# nrfKey_2401.net
KiCad netlist of a schematic drawn in EAGLE
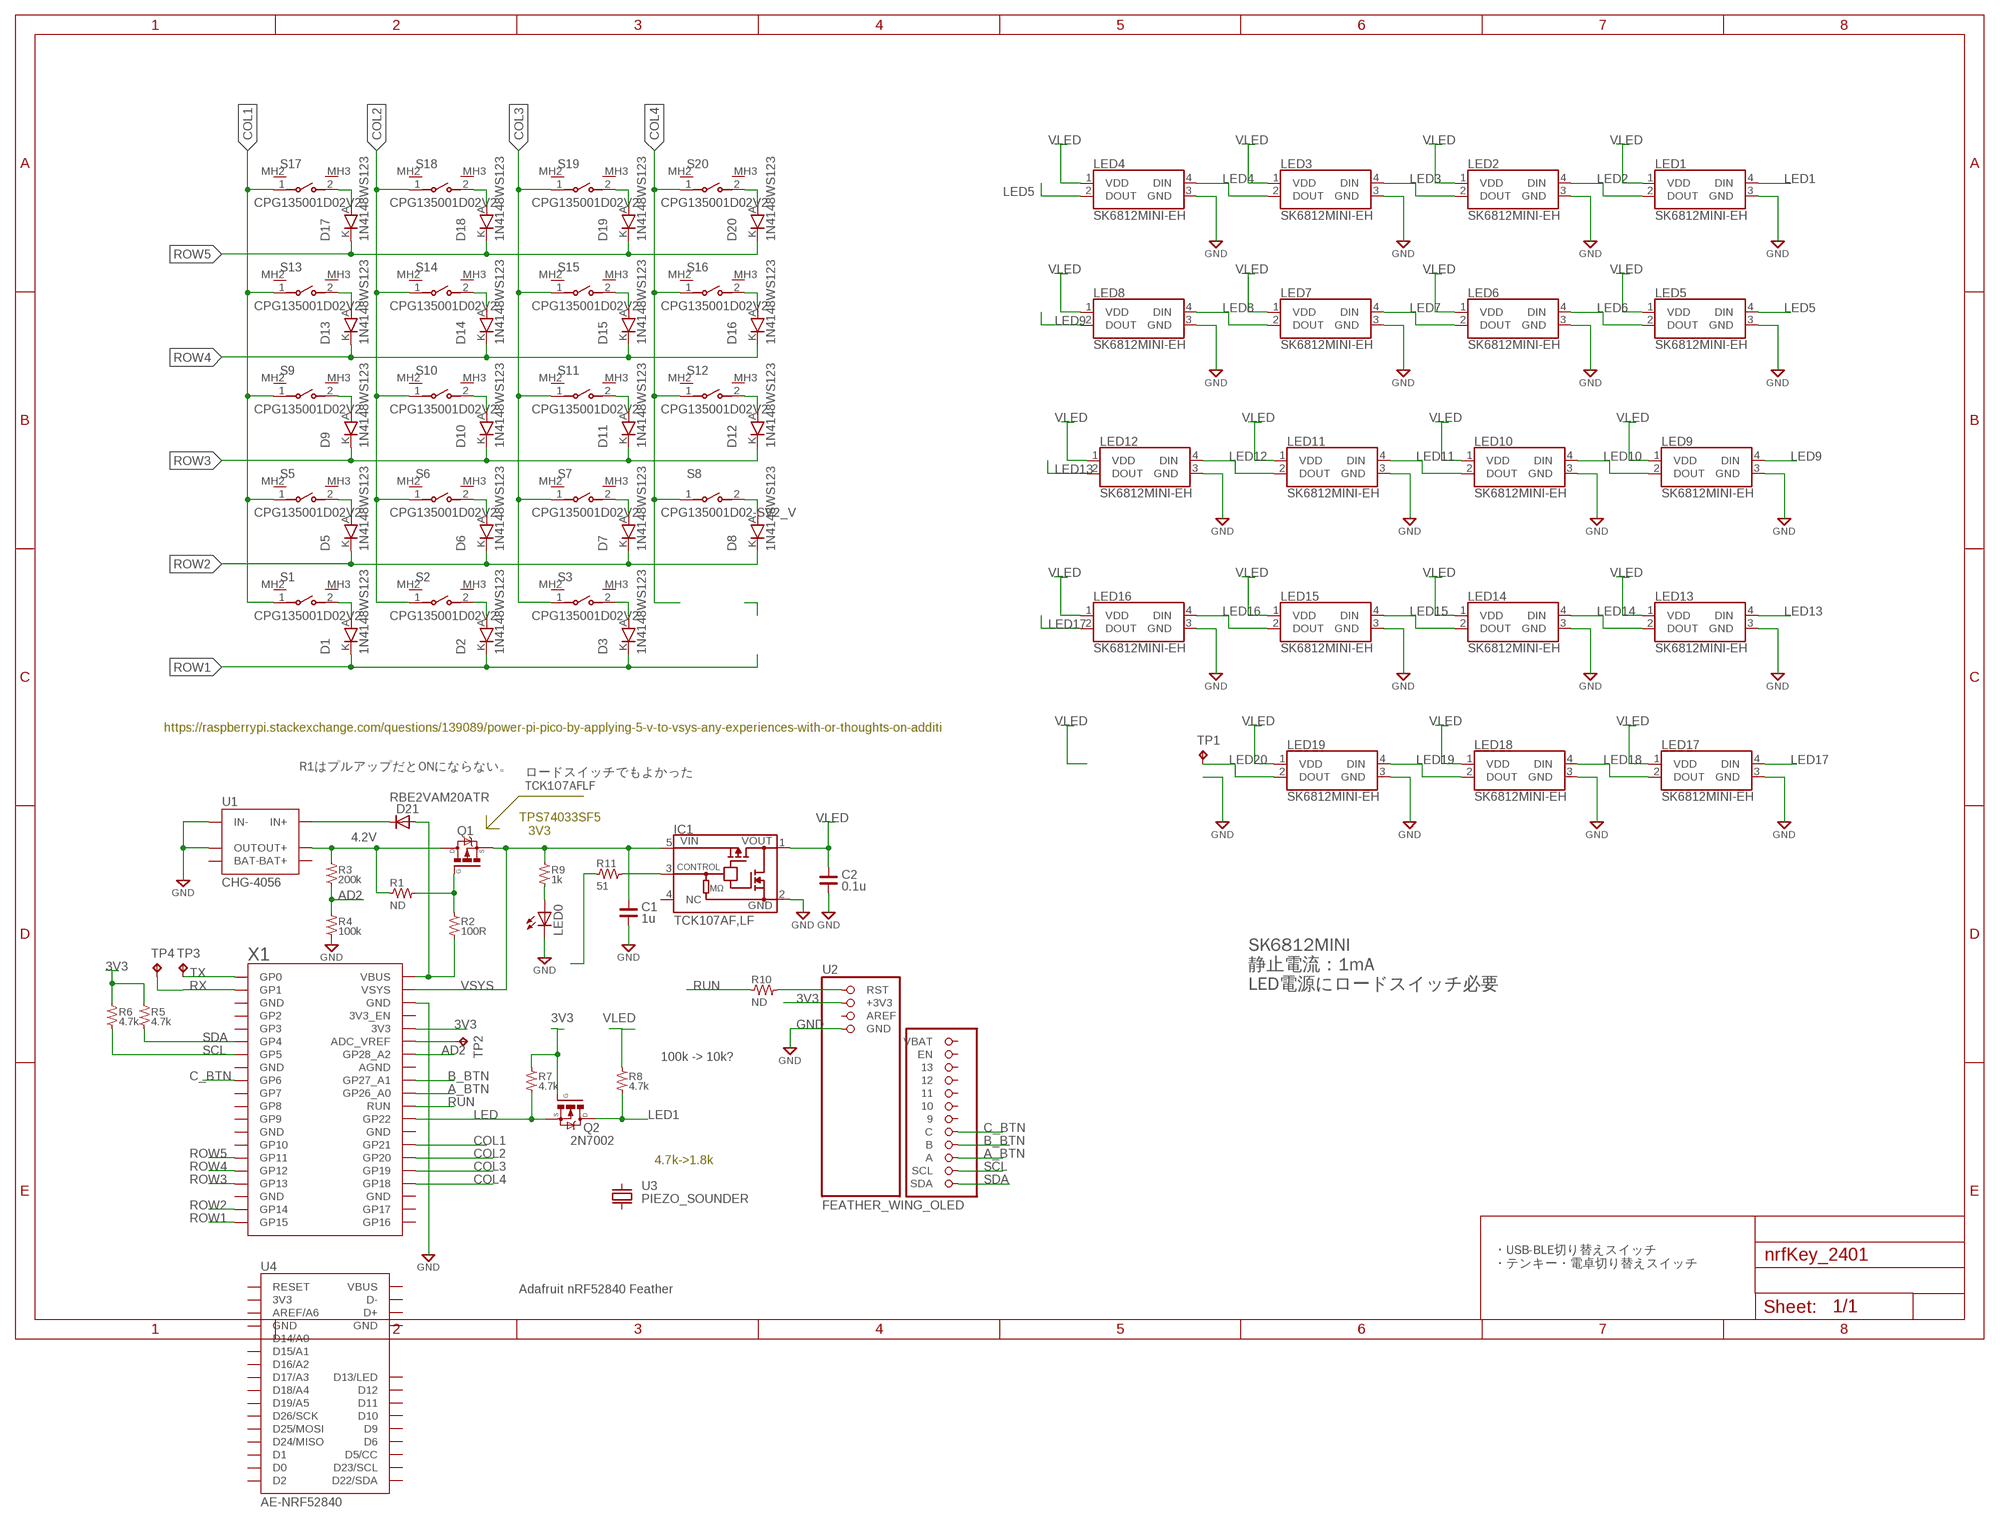
[diagram p0: schematic, sheet 1]

(export (version "E")
  (design (tool "Eeschema 10.0.6"))
  (components
    (comp (ref "C1")
      (value "1u")
      (footprint "eagle-import:C0603")
      (libsource (lib "eagle-import") (part "C_0603"))
    )
    (comp (ref "C2")
      (value "0.1u")
      (footprint "eagle-import:C0603")
      (libsource (lib "eagle-import") (part "C_0603"))
    )
    (comp (ref "D1")
      (value "1N4148WS123")
      (footprint "eagle-import:SOD-123")
      (libsource (lib "eagle-import") (part "1N4148WS123"))
    )
    (comp (ref "D2")
      (value "1N4148WS123")
      (footprint "eagle-import:SOD-123")
      (libsource (lib "eagle-import") (part "1N4148WS123"))
    )
    (comp (ref "D3")
      (value "1N4148WS123")
      (footprint "eagle-import:SOD-123")
      (libsource (lib "eagle-import") (part "1N4148WS123"))
    )
    (comp (ref "D5")
      (value "1N4148WS123")
      (footprint "eagle-import:SOD-123")
      (libsource (lib "eagle-import") (part "1N4148WS123"))
    )
    (comp (ref "D6")
      (value "1N4148WS123")
      (footprint "eagle-import:SOD-123")
      (libsource (lib "eagle-import") (part "1N4148WS123"))
    )
    (comp (ref "D7")
      (value "1N4148WS123")
      (footprint "eagle-import:SOD-123")
      (libsource (lib "eagle-import") (part "1N4148WS123"))
    )
    (comp (ref "D8")
      (value "1N4148WS123")
      (footprint "eagle-import:SOD-123")
      (libsource (lib "eagle-import") (part "1N4148WS123"))
    )
    (comp (ref "D9")
      (value "1N4148WS123")
      (footprint "eagle-import:SOD-123")
      (libsource (lib "eagle-import") (part "1N4148WS123"))
    )
    (comp (ref "D10")
      (value "1N4148WS123")
      (footprint "eagle-import:SOD-123")
      (libsource (lib "eagle-import") (part "1N4148WS123"))
    )
    (comp (ref "D11")
      (value "1N4148WS123")
      (footprint "eagle-import:SOD-123")
      (libsource (lib "eagle-import") (part "1N4148WS123"))
    )
    (comp (ref "D12")
      (value "1N4148WS123")
      (footprint "eagle-import:SOD-123")
      (libsource (lib "eagle-import") (part "1N4148WS123"))
    )
    (comp (ref "D13")
      (value "1N4148WS123")
      (footprint "eagle-import:SOD-123")
      (libsource (lib "eagle-import") (part "1N4148WS123"))
    )
    (comp (ref "D14")
      (value "1N4148WS123")
      (footprint "eagle-import:SOD-123")
      (libsource (lib "eagle-import") (part "1N4148WS123"))
    )
    (comp (ref "D15")
      (value "1N4148WS123")
      (footprint "eagle-import:SOD-123")
      (libsource (lib "eagle-import") (part "1N4148WS123"))
    )
    (comp (ref "D16")
      (value "1N4148WS123")
      (footprint "eagle-import:SOD-123")
      (libsource (lib "eagle-import") (part "1N4148WS123"))
    )
    (comp (ref "D17")
      (value "1N4148WS123")
      (footprint "eagle-import:SOD-123")
      (libsource (lib "eagle-import") (part "1N4148WS123"))
    )
    (comp (ref "D18")
      (value "1N4148WS123")
      (footprint "eagle-import:SOD-123")
      (libsource (lib "eagle-import") (part "1N4148WS123"))
    )
    (comp (ref "D19")
      (value "1N4148WS123")
      (footprint "eagle-import:SOD-123")
      (libsource (lib "eagle-import") (part "1N4148WS123"))
    )
    (comp (ref "D20")
      (value "1N4148WS123")
      (footprint "eagle-import:SOD-123")
      (libsource (lib "eagle-import") (part "1N4148WS123"))
    )
    (comp (ref "D21")
      (value "RBE2VAM20ATR")
      (footprint "eagle-import:SOD-123")
      (libsource (lib "eagle-import") (part "DIODE123"))
    )
    (comp (ref "IC1")
      (value "TCK107AF,LF")
      (footprint "eagle-import:SMV_1")
      (fields
        (field (name "ARROW_PART_NUMBER") "TCK106AF,LF")
        (field (name "MOUSER_PART_NUMBER") "757-TCK106AFLF")
      )
      (libsource (lib "eagle-import") (part "TCK107AF,LF"))
    )
    (comp (ref "LED0")
      (value "LEDCHIP-LED0603")
      (footprint "eagle-import:CHIP-LED0603")
      (libsource (lib "eagle-import") (part "LEDCHIP-LED0603"))
    )
    (comp (ref "LED1")
      (value "SK6812MINI-EH")
      (footprint "eagle-import:SK6812MINIE-H")
      (libsource (lib "eagle-import") (part "SK6812MINI-EH"))
    )
    (comp (ref "LED2")
      (value "SK6812MINI-EH")
      (footprint "eagle-import:SK6812MINIE-H")
      (libsource (lib "eagle-import") (part "SK6812MINI-EH"))
    )
    (comp (ref "LED3")
      (value "SK6812MINI-EH")
      (footprint "eagle-import:SK6812MINIE-H")
      (libsource (lib "eagle-import") (part "SK6812MINI-EH"))
    )
    (comp (ref "LED4")
      (value "SK6812MINI-EH")
      (footprint "eagle-import:SK6812MINIE-H")
      (libsource (lib "eagle-import") (part "SK6812MINI-EH"))
    )
    (comp (ref "LED5")
      (value "SK6812MINI-EH")
      (footprint "eagle-import:SK6812MINIE-H")
      (libsource (lib "eagle-import") (part "SK6812MINI-EH"))
    )
    (comp (ref "LED6")
      (value "SK6812MINI-EH")
      (footprint "eagle-import:SK6812MINIE-H")
      (libsource (lib "eagle-import") (part "SK6812MINI-EH"))
    )
    (comp (ref "LED7")
      (value "SK6812MINI-EH")
      (footprint "eagle-import:SK6812MINIE-H")
      (libsource (lib "eagle-import") (part "SK6812MINI-EH"))
    )
    (comp (ref "LED8")
      (value "SK6812MINI-EH")
      (footprint "eagle-import:SK6812MINIE-H")
      (libsource (lib "eagle-import") (part "SK6812MINI-EH"))
    )
    (comp (ref "LED9")
      (value "SK6812MINI-EH")
      (footprint "eagle-import:SK6812MINIE-H")
      (libsource (lib "eagle-import") (part "SK6812MINI-EH"))
    )
    (comp (ref "LED10")
      (value "SK6812MINI-EH")
      (footprint "eagle-import:SK6812MINIE-H")
      (libsource (lib "eagle-import") (part "SK6812MINI-EH"))
    )
    (comp (ref "LED11")
      (value "SK6812MINI-EH")
      (footprint "eagle-import:SK6812MINIE-H")
      (libsource (lib "eagle-import") (part "SK6812MINI-EH"))
    )
    (comp (ref "LED12")
      (value "SK6812MINI-EH")
      (footprint "eagle-import:SK6812MINIE-H")
      (libsource (lib "eagle-import") (part "SK6812MINI-EH"))
    )
    (comp (ref "LED13")
      (value "SK6812MINI-EH")
      (footprint "eagle-import:SK6812MINIE-H")
      (libsource (lib "eagle-import") (part "SK6812MINI-EH"))
    )
    (comp (ref "LED14")
      (value "SK6812MINI-EH")
      (footprint "eagle-import:SK6812MINIE-H")
      (libsource (lib "eagle-import") (part "SK6812MINI-EH"))
    )
    (comp (ref "LED15")
      (value "SK6812MINI-EH")
      (footprint "eagle-import:SK6812MINIE-H")
      (libsource (lib "eagle-import") (part "SK6812MINI-EH"))
    )
    (comp (ref "LED16")
      (value "SK6812MINI-EH")
      (footprint "eagle-import:SK6812MINIE-H")
      (libsource (lib "eagle-import") (part "SK6812MINI-EH"))
    )
    (comp (ref "LED17")
      (value "SK6812MINI-EH")
      (footprint "eagle-import:SK6812MINIE-H")
      (libsource (lib "eagle-import") (part "SK6812MINI-EH"))
    )
    (comp (ref "LED18")
      (value "SK6812MINI-EH")
      (footprint "eagle-import:SK6812MINIE-H")
      (libsource (lib "eagle-import") (part "SK6812MINI-EH"))
    )
    (comp (ref "LED19")
      (value "SK6812MINI-EH")
      (footprint "eagle-import:SK6812MINIE-H")
      (libsource (lib "eagle-import") (part "SK6812MINI-EH"))
    )
    (comp (ref "Q1")
      (value "MOSFET-P")
      (footprint "eagle-import:SOT-23")
      (libsource (lib "eagle-import") (part "MOSFET-P"))
    )
    (comp (ref "Q2")
      (value "2N7002")
      (footprint "eagle-import:SOT-23")
      (libsource (lib "eagle-import") (part "MOSFET-NSOT-23"))
    )
    (comp (ref "R1")
      (value "ND")
      (footprint "eagle-import:R0603")
      (libsource (lib "eagle-import") (part "R_0603"))
    )
    (comp (ref "R2")
      (value "100R")
      (footprint "eagle-import:R0603")
      (libsource (lib "eagle-import") (part "R_0603"))
    )
    (comp (ref "R3")
      (value "200k")
      (footprint "eagle-import:R0603")
      (libsource (lib "eagle-import") (part "R_0603"))
    )
    (comp (ref "R4")
      (value "100k")
      (footprint "eagle-import:R0603")
      (libsource (lib "eagle-import") (part "R_0603"))
    )
    (comp (ref "R5")
      (value "4.7k")
      (footprint "eagle-import:R0603")
      (libsource (lib "eagle-import") (part "R_0603"))
    )
    (comp (ref "R6")
      (value "4.7k")
      (footprint "eagle-import:R0603")
      (libsource (lib "eagle-import") (part "R_0603"))
    )
    (comp (ref "R7")
      (value "4.7k")
      (footprint "eagle-import:R0603")
      (libsource (lib "eagle-import") (part "R_0603"))
    )
    (comp (ref "R8")
      (value "4.7k")
      (footprint "eagle-import:R0603")
      (libsource (lib "eagle-import") (part "R_0603"))
    )
    (comp (ref "R9")
      (value "1k")
      (footprint "eagle-import:R0603")
      (libsource (lib "eagle-import") (part "R_0603"))
    )
    (comp (ref "R10")
      (value "ND")
      (footprint "eagle-import:R0603")
      (libsource (lib "eagle-import") (part "R_0603"))
    )
    (comp (ref "R11")
      (value "51")
      (footprint "eagle-import:R0603")
      (libsource (lib "eagle-import") (part "R_0603"))
    )
    (comp (ref "S1")
      (value "CPG135001D02V2")
      (footprint "eagle-import:KAILH_CHOC_V2")
      (libsource (lib "eagle-import") (part "CPG135001D02V2"))
    )
    (comp (ref "S2")
      (value "CPG135001D02V2")
      (footprint "eagle-import:KAILH_CHOC_V2")
      (libsource (lib "eagle-import") (part "CPG135001D02V2"))
    )
    (comp (ref "S3")
      (value "CPG135001D02V2")
      (footprint "eagle-import:KAILH_CHOC_V2")
      (libsource (lib "eagle-import") (part "CPG135001D02V2"))
    )
    (comp (ref "S5")
      (value "CPG135001D02V2")
      (footprint "eagle-import:KAILH_CHOC_V2")
      (libsource (lib "eagle-import") (part "CPG135001D02V2"))
    )
    (comp (ref "S6")
      (value "CPG135001D02V2")
      (footprint "eagle-import:KAILH_CHOC_V2")
      (libsource (lib "eagle-import") (part "CPG135001D02V2"))
    )
    (comp (ref "S7")
      (value "CPG135001D02V2")
      (footprint "eagle-import:KAILH_CHOC_V2")
      (libsource (lib "eagle-import") (part "CPG135001D02V2"))
    )
    (comp (ref "S8")
      (value "CPG135001D02-SV2_V")
      (footprint "eagle-import:KAILH_CHOC_V2_V")
      (libsource (lib "eagle-import") (part "CPG135001D02-SV2_V"))
    )
    (comp (ref "S9")
      (value "CPG135001D02V2")
      (footprint "eagle-import:KAILH_CHOC_V2")
      (libsource (lib "eagle-import") (part "CPG135001D02V2"))
    )
    (comp (ref "S10")
      (value "CPG135001D02V2")
      (footprint "eagle-import:KAILH_CHOC_V2")
      (libsource (lib "eagle-import") (part "CPG135001D02V2"))
    )
    (comp (ref "S11")
      (value "CPG135001D02V2")
      (footprint "eagle-import:KAILH_CHOC_V2")
      (libsource (lib "eagle-import") (part "CPG135001D02V2"))
    )
    (comp (ref "S12")
      (value "CPG135001D02V2")
      (footprint "eagle-import:KAILH_CHOC_V2")
      (libsource (lib "eagle-import") (part "CPG135001D02V2"))
    )
    (comp (ref "S13")
      (value "CPG135001D02V2")
      (footprint "eagle-import:KAILH_CHOC_V2")
      (libsource (lib "eagle-import") (part "CPG135001D02V2"))
    )
    (comp (ref "S14")
      (value "CPG135001D02V2")
      (footprint "eagle-import:KAILH_CHOC_V2")
      (libsource (lib "eagle-import") (part "CPG135001D02V2"))
    )
    (comp (ref "S15")
      (value "CPG135001D02V2")
      (footprint "eagle-import:KAILH_CHOC_V2")
      (libsource (lib "eagle-import") (part "CPG135001D02V2"))
    )
    (comp (ref "S16")
      (value "CPG135001D02V2")
      (footprint "eagle-import:KAILH_CHOC_V2")
      (libsource (lib "eagle-import") (part "CPG135001D02V2"))
    )
    (comp (ref "S17")
      (value "CPG135001D02V2")
      (footprint "eagle-import:KAILH_CHOC_V2")
      (libsource (lib "eagle-import") (part "CPG135001D02V2"))
    )
    (comp (ref "S18")
      (value "CPG135001D02V2")
      (footprint "eagle-import:KAILH_CHOC_V2")
      (libsource (lib "eagle-import") (part "CPG135001D02V2"))
    )
    (comp (ref "S19")
      (value "CPG135001D02V2")
      (footprint "eagle-import:KAILH_CHOC_V2")
      (libsource (lib "eagle-import") (part "CPG135001D02V2"))
    )
    (comp (ref "S20")
      (value "CPG135001D02V2")
      (footprint "eagle-import:KAILH_CHOC_V2")
      (libsource (lib "eagle-import") (part "CPG135001D02V2"))
    )
    (comp (ref "TP1")
      (value "TPTP06R")
      (footprint "eagle-import:TP06R")
      (libsource (lib "eagle-import") (part "TPTP06R"))
    )
    (comp (ref "TP2")
      (value "TPTP06R")
      (footprint "eagle-import:TP06R")
      (libsource (lib "eagle-import") (part "TPTP06R"))
    )
    (comp (ref "TP3")
      (value "TPTP06R")
      (footprint "eagle-import:TP06R")
      (libsource (lib "eagle-import") (part "TPTP06R"))
    )
    (comp (ref "TP4")
      (value "TPTP06R")
      (footprint "eagle-import:TP06R")
      (libsource (lib "eagle-import") (part "TPTP06R"))
    )
    (comp (ref "U1")
      (value "CHG-4056")
      (footprint "eagle-import:CHG-4056")
      (libsource (lib "eagle-import") (part "CHG-4056"))
    )
    (comp (ref "U2")
      (value "FEATHER_WING_OLED")
      (footprint "eagle-import:FEATHER_WING_OLED")
      (libsource (lib "eagle-import") (part "FEATHER_WING_OLED"))
    )
    (comp (ref "U3")
      (value "PIEZO_SOUNDER")
      (footprint "eagle-import:DINAMIC-SPK")
      (libsource (lib "eagle-import") (part "PIEZO_SOUNDER"))
    )
    (comp (ref "U4")
      (value "AE-NRF52840")
      (footprint "eagle-import:AE-NRF52840")
      (libsource (lib "eagle-import") (part "AE-NRF52840"))
    )
    (comp (ref "X1")
      (value "RASPBERRYPI_PICO_RPI_PICO_MY-MY")
      (footprint "eagle-import:RASPBERRYPI_PICO_RPI_PICO_MY")
      (libsource (lib "eagle-import") (part "RASPBERRYPI_PICO_RPI_PICO_MY-MY"))
    )
  )
  (nets
    (net (code "1") (name "/3V3") (class "Default")
      (node (ref "Q2") (pin "3") (pinfunction "G_3") (pintype "passive"))
      (node (ref "R5") (pin "2") (pinfunction "2_2") (pintype "passive"))
      (node (ref "R6") (pin "2") (pinfunction "2_2") (pintype "passive"))
      (node (ref "R7") (pin "1") (pinfunction "1_1") (pintype "passive"))
      (node (ref "U2") (pin "15") (pinfunction "+3V3_15") (pintype "passive"))
      (node (ref "X1") (pin "3V3") (pinfunction "3V3_3V3") (pintype "bidirectional"))
    )
    (net (code "2") (name "/4.2V") (class "Default")
      (node (ref "Q1") (pin "2") (pinfunction "D_2") (pintype "passive"))
      (node (ref "R1") (pin "1") (pinfunction "1_1") (pintype "passive"))
      (node (ref "R3") (pin "2") (pinfunction "2_2") (pintype "passive"))
      (node (ref "U1") (pin "OUT+") (pinfunction "OUT+_OUT+") (pintype "bidirectional"))
    )
    (net (code "3") (name "/AD2") (class "Default")
      (node (ref "R3") (pin "1") (pinfunction "1_1") (pintype "passive"))
      (node (ref "R4") (pin "2") (pinfunction "2_2") (pintype "passive"))
      (node (ref "X1") (pin "GP28_A2") (pinfunction "GP28_A2_GP28_A2") (pintype "bidirectional"))
    )
    (net (code "4") (name "/A_BTN") (class "Default")
      (node (ref "U2") (pin "26") (pinfunction "A_26") (pintype "passive"))
      (node (ref "X1") (pin "GP26_A0") (pinfunction "GP26_A0_GP26_A0") (pintype "bidirectional"))
    )
    (net (code "5") (name "/B_BTN") (class "Default")
      (node (ref "U2") (pin "25") (pinfunction "B_25") (pintype "passive"))
      (node (ref "X1") (pin "GP27_A1") (pinfunction "GP27_A1_GP27_A1") (pintype "bidirectional"))
    )
    (net (code "6") (name "/C_BTN") (class "Default")
      (node (ref "U2") (pin "24") (pinfunction "C_24") (pintype "passive"))
      (node (ref "X1") (pin "GP6") (pinfunction "GP6_GP6") (pintype "bidirectional"))
    )
    (net (code "7") (name "/LED") (class "Default")
      (node (ref "Q2") (pin "1") (pinfunction "S_1") (pintype "passive"))
      (node (ref "R7") (pin "2") (pinfunction "2_2") (pintype "passive"))
      (node (ref "X1") (pin "GP22") (pinfunction "GP22_GP22") (pintype "bidirectional"))
    )
    (net (code "8") (name "/LED1") (class "Default")
      (node (ref "LED1") (pin "4") (pinfunction "DIN_4") (pintype "bidirectional"))
      (node (ref "Q2") (pin "2") (pinfunction "D_2") (pintype "passive"))
      (node (ref "R8") (pin "2") (pinfunction "2_2") (pintype "passive"))
    )
    (net (code "9") (name "/LED2") (class "Default")
      (node (ref "LED1") (pin "2") (pinfunction "DOUT_2") (pintype "bidirectional"))
      (node (ref "LED2") (pin "4") (pinfunction "DIN_4") (pintype "bidirectional"))
    )
    (net (code "10") (name "/LED3") (class "Default")
      (node (ref "LED2") (pin "2") (pinfunction "DOUT_2") (pintype "bidirectional"))
      (node (ref "LED3") (pin "4") (pinfunction "DIN_4") (pintype "bidirectional"))
    )
    (net (code "11") (name "/LED4") (class "Default")
      (node (ref "LED3") (pin "2") (pinfunction "DOUT_2") (pintype "bidirectional"))
      (node (ref "LED4") (pin "4") (pinfunction "DIN_4") (pintype "bidirectional"))
    )
    (net (code "12") (name "/LED5") (class "Default")
      (node (ref "LED4") (pin "2") (pinfunction "DOUT_2") (pintype "bidirectional"))
      (node (ref "LED5") (pin "4") (pinfunction "DIN_4") (pintype "bidirectional"))
    )
    (net (code "13") (name "/LED6") (class "Default")
      (node (ref "LED5") (pin "2") (pinfunction "DOUT_2") (pintype "bidirectional"))
      (node (ref "LED6") (pin "4") (pinfunction "DIN_4") (pintype "bidirectional"))
    )
    (net (code "14") (name "/LED7") (class "Default")
      (node (ref "LED6") (pin "2") (pinfunction "DOUT_2") (pintype "bidirectional"))
      (node (ref "LED7") (pin "4") (pinfunction "DIN_4") (pintype "bidirectional"))
    )
    (net (code "15") (name "/LED8") (class "Default")
      (node (ref "LED7") (pin "2") (pinfunction "DOUT_2") (pintype "bidirectional"))
      (node (ref "LED8") (pin "4") (pinfunction "DIN_4") (pintype "bidirectional"))
    )
    (net (code "16") (name "/LED9") (class "Default")
      (node (ref "LED8") (pin "2") (pinfunction "DOUT_2") (pintype "bidirectional"))
      (node (ref "LED9") (pin "4") (pinfunction "DIN_4") (pintype "bidirectional"))
    )
    (net (code "17") (name "/LED10") (class "Default")
      (node (ref "LED10") (pin "4") (pinfunction "DIN_4") (pintype "bidirectional"))
      (node (ref "LED9") (pin "2") (pinfunction "DOUT_2") (pintype "bidirectional"))
    )
    (net (code "18") (name "/LED11") (class "Default")
      (node (ref "LED10") (pin "2") (pinfunction "DOUT_2") (pintype "bidirectional"))
      (node (ref "LED11") (pin "4") (pinfunction "DIN_4") (pintype "bidirectional"))
    )
    (net (code "19") (name "/LED12") (class "Default")
      (node (ref "LED11") (pin "2") (pinfunction "DOUT_2") (pintype "bidirectional"))
      (node (ref "LED12") (pin "4") (pinfunction "DIN_4") (pintype "bidirectional"))
    )
    (net (code "20") (name "/LED13") (class "Default")
      (node (ref "LED12") (pin "2") (pinfunction "DOUT_2") (pintype "bidirectional"))
      (node (ref "LED13") (pin "4") (pinfunction "DIN_4") (pintype "bidirectional"))
    )
    (net (code "21") (name "/LED14") (class "Default")
      (node (ref "LED13") (pin "2") (pinfunction "DOUT_2") (pintype "bidirectional"))
      (node (ref "LED14") (pin "4") (pinfunction "DIN_4") (pintype "bidirectional"))
    )
    (net (code "22") (name "/LED15") (class "Default")
      (node (ref "LED14") (pin "2") (pinfunction "DOUT_2") (pintype "bidirectional"))
      (node (ref "LED15") (pin "4") (pinfunction "DIN_4") (pintype "bidirectional"))
    )
    (net (code "23") (name "/LED16") (class "Default")
      (node (ref "LED15") (pin "2") (pinfunction "DOUT_2") (pintype "bidirectional"))
      (node (ref "LED16") (pin "4") (pinfunction "DIN_4") (pintype "bidirectional"))
    )
    (net (code "24") (name "/LED17") (class "Default")
      (node (ref "LED16") (pin "2") (pinfunction "DOUT_2") (pintype "bidirectional"))
      (node (ref "LED17") (pin "4") (pinfunction "DIN_4") (pintype "bidirectional"))
    )
    (net (code "25") (name "/LED18") (class "Default")
      (node (ref "LED17") (pin "2") (pinfunction "DOUT_2") (pintype "bidirectional"))
      (node (ref "LED18") (pin "4") (pinfunction "DIN_4") (pintype "bidirectional"))
    )
    (net (code "26") (name "/LED19") (class "Default")
      (node (ref "LED18") (pin "2") (pinfunction "DOUT_2") (pintype "bidirectional"))
      (node (ref "LED19") (pin "4") (pinfunction "DIN_4") (pintype "bidirectional"))
    )
    (net (code "27") (name "/LED20") (class "Default")
      (node (ref "LED19") (pin "2") (pinfunction "DOUT_2") (pintype "bidirectional"))
      (node (ref "TP1") (pin "TP") (pinfunction "TP_TP") (pintype "input"))
    )
    (net (code "28") (name "/RUN") (class "Default")
      (node (ref "R10") (pin "1") (pinfunction "1_1") (pintype "passive"))
      (node (ref "X1") (pin "RUN") (pinfunction "RUN_RUN") (pintype "bidirectional"))
    )
    (net (code "29") (name "/RX") (class "Default")
      (node (ref "TP4") (pin "TP") (pinfunction "TP_TP") (pintype "input"))
      (node (ref "X1") (pin "GP1") (pinfunction "GP1_GP1") (pintype "bidirectional"))
    )
    (net (code "30") (name "/SCL") (class "Default")
      (node (ref "R6") (pin "1") (pinfunction "1_1") (pintype "passive"))
      (node (ref "U2") (pin "27") (pinfunction "SCL_27") (pintype "passive"))
      (node (ref "X1") (pin "GP5") (pinfunction "GP5_GP5") (pintype "bidirectional"))
    )
    (net (code "31") (name "/SDA") (class "Default")
      (node (ref "R5") (pin "1") (pinfunction "1_1") (pintype "passive"))
      (node (ref "U2") (pin "28") (pinfunction "SDA_28") (pintype "passive"))
      (node (ref "X1") (pin "GP4") (pinfunction "GP4_GP4") (pintype "bidirectional"))
    )
    (net (code "32") (name "/TX") (class "Default")
      (node (ref "TP3") (pin "TP") (pinfunction "TP_TP") (pintype "input"))
      (node (ref "X1") (pin "GP0") (pinfunction "GP0_GP0") (pintype "bidirectional"))
    )
    (net (code "33") (name "/VLED") (class "Default")
      (node (ref "C2") (pin "2") (pinfunction "2_2") (pintype "passive"))
      (node (ref "IC1") (pin "1") (pinfunction "VOUT_1") (pintype "bidirectional"))
      (node (ref "LED1") (pin "1") (pinfunction "VDD_1") (pintype "bidirectional"))
      (node (ref "LED10") (pin "1") (pinfunction "VDD_1") (pintype "bidirectional"))
      (node (ref "LED11") (pin "1") (pinfunction "VDD_1") (pintype "bidirectional"))
      (node (ref "LED12") (pin "1") (pinfunction "VDD_1") (pintype "bidirectional"))
      (node (ref "LED13") (pin "1") (pinfunction "VDD_1") (pintype "bidirectional"))
      (node (ref "LED14") (pin "1") (pinfunction "VDD_1") (pintype "bidirectional"))
      (node (ref "LED15") (pin "1") (pinfunction "VDD_1") (pintype "bidirectional"))
      (node (ref "LED16") (pin "1") (pinfunction "VDD_1") (pintype "bidirectional"))
      (node (ref "LED17") (pin "1") (pinfunction "VDD_1") (pintype "bidirectional"))
      (node (ref "LED18") (pin "1") (pinfunction "VDD_1") (pintype "bidirectional"))
      (node (ref "LED19") (pin "1") (pinfunction "VDD_1") (pintype "bidirectional"))
      (node (ref "LED2") (pin "1") (pinfunction "VDD_1") (pintype "bidirectional"))
      (node (ref "LED3") (pin "1") (pinfunction "VDD_1") (pintype "bidirectional"))
      (node (ref "LED4") (pin "1") (pinfunction "VDD_1") (pintype "bidirectional"))
      (node (ref "LED5") (pin "1") (pinfunction "VDD_1") (pintype "bidirectional"))
      (node (ref "LED6") (pin "1") (pinfunction "VDD_1") (pintype "bidirectional"))
      (node (ref "LED7") (pin "1") (pinfunction "VDD_1") (pintype "bidirectional"))
      (node (ref "LED8") (pin "1") (pinfunction "VDD_1") (pintype "bidirectional"))
      (node (ref "LED9") (pin "1") (pinfunction "VDD_1") (pintype "bidirectional"))
      (node (ref "R8") (pin "1") (pinfunction "1_1") (pintype "passive"))
    )
    (net (code "34") (name "/VSYS") (class "Default")
      (node (ref "C1") (pin "2") (pinfunction "2_2") (pintype "passive"))
      (node (ref "IC1") (pin "5") (pinfunction "VIN_5") (pintype "bidirectional"))
      (node (ref "Q1") (pin "1") (pinfunction "S_1") (pintype "passive"))
      (node (ref "R9") (pin "1") (pinfunction "1_1") (pintype "passive"))
      (node (ref "X1") (pin "VSYS") (pinfunction "VSYS_VSYS") (pintype "bidirectional"))
    )
    (net (code "35") (name "COL1") (class "Default")
      (node (ref "S1") (pin "1") (pinfunction "1_1") (pintype "bidirectional"))
      (node (ref "S13") (pin "1") (pinfunction "1_1") (pintype "bidirectional"))
      (node (ref "S17") (pin "1") (pinfunction "1_1") (pintype "bidirectional"))
      (node (ref "S5") (pin "1") (pinfunction "1_1") (pintype "bidirectional"))
      (node (ref "S9") (pin "1") (pinfunction "1_1") (pintype "bidirectional"))
      (node (ref "X1") (pin "GP21") (pinfunction "GP21_GP21") (pintype "bidirectional"))
    )
    (net (code "36") (name "COL2") (class "Default")
      (node (ref "S10") (pin "1") (pinfunction "1_1") (pintype "bidirectional"))
      (node (ref "S14") (pin "1") (pinfunction "1_1") (pintype "bidirectional"))
      (node (ref "S18") (pin "1") (pinfunction "1_1") (pintype "bidirectional"))
      (node (ref "S2") (pin "1") (pinfunction "1_1") (pintype "bidirectional"))
      (node (ref "S6") (pin "1") (pinfunction "1_1") (pintype "bidirectional"))
      (node (ref "X1") (pin "GP20") (pinfunction "GP20_GP20") (pintype "bidirectional"))
    )
    (net (code "37") (name "COL3") (class "Default")
      (node (ref "S11") (pin "1") (pinfunction "1_1") (pintype "bidirectional"))
      (node (ref "S15") (pin "1") (pinfunction "1_1") (pintype "bidirectional"))
      (node (ref "S19") (pin "1") (pinfunction "1_1") (pintype "bidirectional"))
      (node (ref "S3") (pin "1") (pinfunction "1_1") (pintype "bidirectional"))
      (node (ref "S7") (pin "1") (pinfunction "1_1") (pintype "bidirectional"))
      (node (ref "X1") (pin "GP19") (pinfunction "GP19_GP19") (pintype "bidirectional"))
    )
    (net (code "38") (name "COL4") (class "Default")
      (node (ref "S12") (pin "1") (pinfunction "1_1") (pintype "bidirectional"))
      (node (ref "S16") (pin "1") (pinfunction "1_1") (pintype "bidirectional"))
      (node (ref "S20") (pin "1") (pinfunction "1_1") (pintype "bidirectional"))
      (node (ref "S8") (pin "1") (pinfunction "1_1") (pintype "bidirectional"))
      (node (ref "X1") (pin "GP18") (pinfunction "GP18_GP18") (pintype "bidirectional"))
    )
    (net (code "39") (name "G") (class "Default")
      (node (ref "C1") (pin "1") (pinfunction "1_1") (pintype "passive"))
      (node (ref "C2") (pin "1") (pinfunction "1_1") (pintype "passive"))
      (node (ref "IC1") (pin "2") (pinfunction "GND_2") (pintype "bidirectional"))
      (node (ref "LED0") (pin "C") (pinfunction "C_C") (pintype "passive"))
      (node (ref "LED1") (pin "3") (pinfunction "GND_3") (pintype "bidirectional"))
      (node (ref "LED10") (pin "3") (pinfunction "GND_3") (pintype "bidirectional"))
      (node (ref "LED11") (pin "3") (pinfunction "GND_3") (pintype "bidirectional"))
      (node (ref "LED12") (pin "3") (pinfunction "GND_3") (pintype "bidirectional"))
      (node (ref "LED13") (pin "3") (pinfunction "GND_3") (pintype "bidirectional"))
      (node (ref "LED14") (pin "3") (pinfunction "GND_3") (pintype "bidirectional"))
      (node (ref "LED15") (pin "3") (pinfunction "GND_3") (pintype "bidirectional"))
      (node (ref "LED16") (pin "3") (pinfunction "GND_3") (pintype "bidirectional"))
      (node (ref "LED17") (pin "3") (pinfunction "GND_3") (pintype "bidirectional"))
      (node (ref "LED18") (pin "3") (pinfunction "GND_3") (pintype "bidirectional"))
      (node (ref "LED19") (pin "3") (pinfunction "GND_3") (pintype "bidirectional"))
      (node (ref "LED2") (pin "3") (pinfunction "GND_3") (pintype "bidirectional"))
      (node (ref "LED3") (pin "3") (pinfunction "GND_3") (pintype "bidirectional"))
      (node (ref "LED4") (pin "3") (pinfunction "GND_3") (pintype "bidirectional"))
      (node (ref "LED5") (pin "3") (pinfunction "GND_3") (pintype "bidirectional"))
      (node (ref "LED6") (pin "3") (pinfunction "GND_3") (pintype "bidirectional"))
      (node (ref "LED7") (pin "3") (pinfunction "GND_3") (pintype "bidirectional"))
      (node (ref "LED8") (pin "3") (pinfunction "GND_3") (pintype "bidirectional"))
      (node (ref "LED9") (pin "3") (pinfunction "GND_3") (pintype "bidirectional"))
      (node (ref "R4") (pin "1") (pinfunction "1_1") (pintype "passive"))
      (node (ref "U1") (pin "IN-") (pinfunction "IN-_IN-") (pintype "bidirectional"))
      (node (ref "U1") (pin "OUT-") (pinfunction "OUT-_OUT-") (pintype "bidirectional"))
      (node (ref "U2") (pin "13") (pinfunction "GND_13") (pintype "passive"))
      (node (ref "X1") (pin "GND@8") (pinfunction "GND_GND@8") (pintype "bidirectional"))
    )
    (net (code "40") (name "Net-(D1-PadA)") (class "Default")
      (node (ref "D1") (pin "A") (pinfunction "A_A") (pintype "bidirectional"))
      (node (ref "S1") (pin "2") (pinfunction "2_2") (pintype "bidirectional"))
    )
    (net (code "41") (name "Net-(D2-PadA)") (class "Default")
      (node (ref "D2") (pin "A") (pinfunction "A_A") (pintype "bidirectional"))
      (node (ref "S2") (pin "2") (pinfunction "2_2") (pintype "bidirectional"))
    )
    (net (code "42") (name "Net-(D3-PadA)") (class "Default")
      (node (ref "D3") (pin "A") (pinfunction "A_A") (pintype "bidirectional"))
      (node (ref "S3") (pin "2") (pinfunction "2_2") (pintype "bidirectional"))
    )
    (net (code "43") (name "Net-(D5-PadA)") (class "Default")
      (node (ref "D5") (pin "A") (pinfunction "A_A") (pintype "bidirectional"))
      (node (ref "S5") (pin "2") (pinfunction "2_2") (pintype "bidirectional"))
    )
    (net (code "44") (name "Net-(D6-PadA)") (class "Default")
      (node (ref "D6") (pin "A") (pinfunction "A_A") (pintype "bidirectional"))
      (node (ref "S6") (pin "2") (pinfunction "2_2") (pintype "bidirectional"))
    )
    (net (code "45") (name "Net-(D7-PadA)") (class "Default")
      (node (ref "D7") (pin "A") (pinfunction "A_A") (pintype "bidirectional"))
      (node (ref "S7") (pin "2") (pinfunction "2_2") (pintype "bidirectional"))
    )
    (net (code "46") (name "Net-(D8-PadA)") (class "Default")
      (node (ref "D8") (pin "A") (pinfunction "A_A") (pintype "bidirectional"))
      (node (ref "S8") (pin "2") (pinfunction "2_2") (pintype "bidirectional"))
    )
    (net (code "47") (name "Net-(D9-PadA)") (class "Default")
      (node (ref "D9") (pin "A") (pinfunction "A_A") (pintype "bidirectional"))
      (node (ref "S9") (pin "2") (pinfunction "2_2") (pintype "bidirectional"))
    )
    (net (code "48") (name "Net-(D10-PadA)") (class "Default")
      (node (ref "D10") (pin "A") (pinfunction "A_A") (pintype "bidirectional"))
      (node (ref "S10") (pin "2") (pinfunction "2_2") (pintype "bidirectional"))
    )
    (net (code "49") (name "Net-(D11-PadA)") (class "Default")
      (node (ref "D11") (pin "A") (pinfunction "A_A") (pintype "bidirectional"))
      (node (ref "S11") (pin "2") (pinfunction "2_2") (pintype "bidirectional"))
    )
    (net (code "50") (name "Net-(D12-PadA)") (class "Default")
      (node (ref "D12") (pin "A") (pinfunction "A_A") (pintype "bidirectional"))
      (node (ref "S12") (pin "2") (pinfunction "2_2") (pintype "bidirectional"))
    )
    (net (code "51") (name "Net-(D13-PadA)") (class "Default")
      (node (ref "D13") (pin "A") (pinfunction "A_A") (pintype "bidirectional"))
      (node (ref "S13") (pin "2") (pinfunction "2_2") (pintype "bidirectional"))
    )
    (net (code "52") (name "Net-(D14-PadA)") (class "Default")
      (node (ref "D14") (pin "A") (pinfunction "A_A") (pintype "bidirectional"))
      (node (ref "S14") (pin "2") (pinfunction "2_2") (pintype "bidirectional"))
    )
    (net (code "53") (name "Net-(D15-PadA)") (class "Default")
      (node (ref "D15") (pin "A") (pinfunction "A_A") (pintype "bidirectional"))
      (node (ref "S15") (pin "2") (pinfunction "2_2") (pintype "bidirectional"))
    )
    (net (code "54") (name "Net-(D16-PadA)") (class "Default")
      (node (ref "D16") (pin "A") (pinfunction "A_A") (pintype "bidirectional"))
      (node (ref "S16") (pin "2") (pinfunction "2_2") (pintype "bidirectional"))
    )
    (net (code "55") (name "Net-(D17-PadA)") (class "Default")
      (node (ref "D17") (pin "A") (pinfunction "A_A") (pintype "bidirectional"))
      (node (ref "S17") (pin "2") (pinfunction "2_2") (pintype "bidirectional"))
    )
    (net (code "56") (name "Net-(D18-PadA)") (class "Default")
      (node (ref "D18") (pin "A") (pinfunction "A_A") (pintype "bidirectional"))
      (node (ref "S18") (pin "2") (pinfunction "2_2") (pintype "bidirectional"))
    )
    (net (code "57") (name "Net-(D19-PadA)") (class "Default")
      (node (ref "D19") (pin "A") (pinfunction "A_A") (pintype "bidirectional"))
      (node (ref "S19") (pin "2") (pinfunction "2_2") (pintype "bidirectional"))
    )
    (net (code "58") (name "Net-(D20-PadA)") (class "Default")
      (node (ref "D20") (pin "A") (pinfunction "A_A") (pintype "bidirectional"))
      (node (ref "S20") (pin "2") (pinfunction "2_2") (pintype "bidirectional"))
    )
    (net (code "59") (name "Net-(D21-C)") (class "Default")
      (node (ref "D21") (pin "K") (pinfunction "C_K") (pintype "passive"))
      (node (ref "U1") (pin "IN+") (pinfunction "IN+_IN+") (pintype "bidirectional"))
    )
    (net (code "60") (name "Net-(D21-PadA)") (class "Default")
      (node (ref "D21") (pin "A") (pinfunction "A_A") (pintype "passive"))
      (node (ref "R2") (pin "2") (pinfunction "2_2") (pintype "passive"))
      (node (ref "X1") (pin "VBUS") (pinfunction "VBUS_VBUS") (pintype "bidirectional"))
    )
    (net (code "61") (name "Net-(IC1-CONTROL)") (class "Default")
      (node (ref "IC1") (pin "3") (pinfunction "CONTROL_3") (pintype "bidirectional"))
      (node (ref "R11") (pin "2") (pinfunction "2_2") (pintype "passive"))
    )
    (net (code "62") (name "Net-(LED0-PadA)") (class "Default")
      (node (ref "LED0") (pin "A") (pinfunction "A_A") (pintype "passive"))
      (node (ref "R9") (pin "2") (pinfunction "2_2") (pintype "passive"))
    )
    (net (code "63") (name "Net-(Q1-G)") (class "Default")
      (node (ref "Q1") (pin "3") (pinfunction "G_3") (pintype "passive"))
      (node (ref "R1") (pin "2") (pinfunction "2_2") (pintype "passive"))
      (node (ref "R2") (pin "1") (pinfunction "1_1") (pintype "passive"))
    )
    (net (code "64") (name "Net-(TP2-PadTP)") (class "Default")
      (node (ref "TP2") (pin "TP") (pinfunction "TP_TP") (pintype "input"))
      (node (ref "X1") (pin "ADC_VREF") (pinfunction "ADC_VREF_ADC_VREF") (pintype "bidirectional"))
    )
    (net (code "65") (name "Net-(U2-RST)") (class "Default")
      (node (ref "R10") (pin "2") (pinfunction "2_2") (pintype "passive"))
      (node (ref "U2") (pin "16") (pinfunction "RST_16") (pintype "passive"))
    )
    (net (code "66") (name "ROW1") (class "Default")
      (node (ref "D1") (pin "K") (pinfunction "K_K") (pintype "bidirectional"))
      (node (ref "D2") (pin "K") (pinfunction "K_K") (pintype "bidirectional"))
      (node (ref "D3") (pin "K") (pinfunction "K_K") (pintype "bidirectional"))
      (node (ref "X1") (pin "GP15") (pinfunction "GP15_GP15") (pintype "bidirectional"))
    )
    (net (code "67") (name "ROW2") (class "Default")
      (node (ref "D5") (pin "K") (pinfunction "K_K") (pintype "bidirectional"))
      (node (ref "D6") (pin "K") (pinfunction "K_K") (pintype "bidirectional"))
      (node (ref "D7") (pin "K") (pinfunction "K_K") (pintype "bidirectional"))
      (node (ref "D8") (pin "K") (pinfunction "K_K") (pintype "bidirectional"))
      (node (ref "X1") (pin "GP14") (pinfunction "GP14_GP14") (pintype "bidirectional"))
    )
    (net (code "68") (name "ROW3") (class "Default")
      (node (ref "D10") (pin "K") (pinfunction "K_K") (pintype "bidirectional"))
      (node (ref "D11") (pin "K") (pinfunction "K_K") (pintype "bidirectional"))
      (node (ref "D12") (pin "K") (pinfunction "K_K") (pintype "bidirectional"))
      (node (ref "D9") (pin "K") (pinfunction "K_K") (pintype "bidirectional"))
      (node (ref "X1") (pin "GP13") (pinfunction "GP13_GP13") (pintype "bidirectional"))
    )
    (net (code "69") (name "ROW4") (class "Default")
      (node (ref "D13") (pin "K") (pinfunction "K_K") (pintype "bidirectional"))
      (node (ref "D14") (pin "K") (pinfunction "K_K") (pintype "bidirectional"))
      (node (ref "D15") (pin "K") (pinfunction "K_K") (pintype "bidirectional"))
      (node (ref "D16") (pin "K") (pinfunction "K_K") (pintype "bidirectional"))
      (node (ref "X1") (pin "GP12") (pinfunction "GP12_GP12") (pintype "bidirectional"))
    )
    (net (code "70") (name "ROW5") (class "Default")
      (node (ref "D17") (pin "K") (pinfunction "K_K") (pintype "bidirectional"))
      (node (ref "D18") (pin "K") (pinfunction "K_K") (pintype "bidirectional"))
      (node (ref "D19") (pin "K") (pinfunction "K_K") (pintype "bidirectional"))
      (node (ref "D20") (pin "K") (pinfunction "K_K") (pintype "bidirectional"))
      (node (ref "X1") (pin "GP11") (pinfunction "GP11_GP11") (pintype "bidirectional"))
    )
    (net (code "71") (name "unconnected-(IC1-NC-Pad4)") (class "Default")
      (node (ref "IC1") (pin "4") (pinfunction "NC_4") (pintype "no_connect"))
    )
    (net (code "72") (name "unconnected-(R11-Pad1)") (class "Default")
      (node (ref "R11") (pin "1") (pinfunction "1_1") (pintype "passive"))
    )
    (net (code "73") (name "unconnected-(S1-MH-PadMH2)") (class "Default")
      (node (ref "S1") (pin "MH2") (pinfunction "MH_MH2") (pintype "bidirectional"))
    )
    (net (code "74") (name "unconnected-(S1-MH-PadMH3)") (class "Default")
      (node (ref "S1") (pin "MH3") (pinfunction "MH_MH3") (pintype "bidirectional"))
    )
    (net (code "75") (name "unconnected-(S2-MH-PadMH2)") (class "Default")
      (node (ref "S2") (pin "MH2") (pinfunction "MH_MH2") (pintype "bidirectional"))
    )
    (net (code "76") (name "unconnected-(S2-MH-PadMH3)") (class "Default")
      (node (ref "S2") (pin "MH3") (pinfunction "MH_MH3") (pintype "bidirectional"))
    )
    (net (code "77") (name "unconnected-(S3-MH-PadMH2)") (class "Default")
      (node (ref "S3") (pin "MH2") (pinfunction "MH_MH2") (pintype "bidirectional"))
    )
    (net (code "78") (name "unconnected-(S3-MH-PadMH3)") (class "Default")
      (node (ref "S3") (pin "MH3") (pinfunction "MH_MH3") (pintype "bidirectional"))
    )
    (net (code "79") (name "unconnected-(S5-MH-PadMH2)") (class "Default")
      (node (ref "S5") (pin "MH2") (pinfunction "MH_MH2") (pintype "bidirectional"))
    )
    (net (code "80") (name "unconnected-(S5-MH-PadMH3)") (class "Default")
      (node (ref "S5") (pin "MH3") (pinfunction "MH_MH3") (pintype "bidirectional"))
    )
    (net (code "81") (name "unconnected-(S6-MH-PadMH2)") (class "Default")
      (node (ref "S6") (pin "MH2") (pinfunction "MH_MH2") (pintype "bidirectional"))
    )
    (net (code "82") (name "unconnected-(S6-MH-PadMH3)") (class "Default")
      (node (ref "S6") (pin "MH3") (pinfunction "MH_MH3") (pintype "bidirectional"))
    )
    (net (code "83") (name "unconnected-(S7-MH-PadMH2)") (class "Default")
      (node (ref "S7") (pin "MH2") (pinfunction "MH_MH2") (pintype "bidirectional"))
    )
    (net (code "84") (name "unconnected-(S7-MH-PadMH3)") (class "Default")
      (node (ref "S7") (pin "MH3") (pinfunction "MH_MH3") (pintype "bidirectional"))
    )
    (net (code "85") (name "unconnected-(S9-MH-PadMH2)") (class "Default")
      (node (ref "S9") (pin "MH2") (pinfunction "MH_MH2") (pintype "bidirectional"))
    )
    (net (code "86") (name "unconnected-(S9-MH-PadMH3)") (class "Default")
      (node (ref "S9") (pin "MH3") (pinfunction "MH_MH3") (pintype "bidirectional"))
    )
    (net (code "87") (name "unconnected-(S10-MH-PadMH2)") (class "Default")
      (node (ref "S10") (pin "MH2") (pinfunction "MH_MH2") (pintype "bidirectional"))
    )
    (net (code "88") (name "unconnected-(S10-MH-PadMH3)") (class "Default")
      (node (ref "S10") (pin "MH3") (pinfunction "MH_MH3") (pintype "bidirectional"))
    )
    (net (code "89") (name "unconnected-(S11-MH-PadMH2)") (class "Default")
      (node (ref "S11") (pin "MH2") (pinfunction "MH_MH2") (pintype "bidirectional"))
    )
    (net (code "90") (name "unconnected-(S11-MH-PadMH3)") (class "Default")
      (node (ref "S11") (pin "MH3") (pinfunction "MH_MH3") (pintype "bidirectional"))
    )
    (net (code "91") (name "unconnected-(S12-MH-PadMH2)") (class "Default")
      (node (ref "S12") (pin "MH2") (pinfunction "MH_MH2") (pintype "bidirectional"))
    )
    (net (code "92") (name "unconnected-(S12-MH-PadMH3)") (class "Default")
      (node (ref "S12") (pin "MH3") (pinfunction "MH_MH3") (pintype "bidirectional"))
    )
    (net (code "93") (name "unconnected-(S13-MH-PadMH2)") (class "Default")
      (node (ref "S13") (pin "MH2") (pinfunction "MH_MH2") (pintype "bidirectional"))
    )
    (net (code "94") (name "unconnected-(S13-MH-PadMH3)") (class "Default")
      (node (ref "S13") (pin "MH3") (pinfunction "MH_MH3") (pintype "bidirectional"))
    )
    (net (code "95") (name "unconnected-(S14-MH-PadMH2)") (class "Default")
      (node (ref "S14") (pin "MH2") (pinfunction "MH_MH2") (pintype "bidirectional"))
    )
    (net (code "96") (name "unconnected-(S14-MH-PadMH3)") (class "Default")
      (node (ref "S14") (pin "MH3") (pinfunction "MH_MH3") (pintype "bidirectional"))
    )
    (net (code "97") (name "unconnected-(S15-MH-PadMH2)") (class "Default")
      (node (ref "S15") (pin "MH2") (pinfunction "MH_MH2") (pintype "bidirectional"))
    )
    (net (code "98") (name "unconnected-(S15-MH-PadMH3)") (class "Default")
      (node (ref "S15") (pin "MH3") (pinfunction "MH_MH3") (pintype "bidirectional"))
    )
    (net (code "99") (name "unconnected-(S16-MH-PadMH2)") (class "Default")
      (node (ref "S16") (pin "MH2") (pinfunction "MH_MH2") (pintype "bidirectional"))
    )
    (net (code "100") (name "unconnected-(S16-MH-PadMH3)") (class "Default")
      (node (ref "S16") (pin "MH3") (pinfunction "MH_MH3") (pintype "bidirectional"))
    )
    (net (code "101") (name "unconnected-(S17-MH-PadMH2)") (class "Default")
      (node (ref "S17") (pin "MH2") (pinfunction "MH_MH2") (pintype "bidirectional"))
    )
    (net (code "102") (name "unconnected-(S17-MH-PadMH3)") (class "Default")
      (node (ref "S17") (pin "MH3") (pinfunction "MH_MH3") (pintype "bidirectional"))
    )
    (net (code "103") (name "unconnected-(S18-MH-PadMH2)") (class "Default")
      (node (ref "S18") (pin "MH2") (pinfunction "MH_MH2") (pintype "bidirectional"))
    )
    (net (code "104") (name "unconnected-(S18-MH-PadMH3)") (class "Default")
      (node (ref "S18") (pin "MH3") (pinfunction "MH_MH3") (pintype "bidirectional"))
    )
    (net (code "105") (name "unconnected-(S19-MH-PadMH2)") (class "Default")
      (node (ref "S19") (pin "MH2") (pinfunction "MH_MH2") (pintype "bidirectional"))
    )
    (net (code "106") (name "unconnected-(S19-MH-PadMH3)") (class "Default")
      (node (ref "S19") (pin "MH3") (pinfunction "MH_MH3") (pintype "bidirectional"))
    )
    (net (code "107") (name "unconnected-(S20-MH-PadMH2)") (class "Default")
      (node (ref "S20") (pin "MH2") (pinfunction "MH_MH2") (pintype "bidirectional"))
    )
    (net (code "108") (name "unconnected-(S20-MH-PadMH3)") (class "Default")
      (node (ref "S20") (pin "MH3") (pinfunction "MH_MH3") (pintype "bidirectional"))
    )
    (net (code "109") (name "unconnected-(U1-PadBAT+)") (class "Default")
      (node (ref "U1") (pin "BAT+") (pinfunction "BAT+_BAT+") (pintype "bidirectional"))
    )
    (net (code "110") (name "unconnected-(U1-PadBAT-)") (class "Default")
      (node (ref "U1") (pin "BAT-") (pinfunction "BAT-_BAT-") (pintype "bidirectional"))
    )
    (net (code "111") (name "unconnected-(U2-9-Pad23)") (class "Default")
      (node (ref "U2") (pin "23") (pinfunction "9_23") (pintype "passive"))
    )
    (net (code "112") (name "unconnected-(U2-10-Pad22)") (class "Default")
      (node (ref "U2") (pin "22") (pinfunction "10_22") (pintype "passive"))
    )
    (net (code "113") (name "unconnected-(U2-11-Pad21)") (class "Default")
      (node (ref "U2") (pin "21") (pinfunction "11_21") (pintype "passive"))
    )
    (net (code "114") (name "unconnected-(U2-12-Pad20)") (class "Default")
      (node (ref "U2") (pin "20") (pinfunction "12_20") (pintype "passive"))
    )
    (net (code "115") (name "unconnected-(U2-13-Pad19)") (class "Default")
      (node (ref "U2") (pin "19") (pinfunction "13_19") (pintype "passive"))
    )
    (net (code "116") (name "unconnected-(U2-AREF-Pad14)") (class "Default")
      (node (ref "U2") (pin "14") (pinfunction "AREF_14") (pintype "passive"))
    )
    (net (code "117") (name "unconnected-(U2-EN-Pad18)") (class "Default")
      (node (ref "U2") (pin "18") (pinfunction "EN_18") (pintype "passive"))
    )
    (net (code "118") (name "unconnected-(U2-VBAT-Pad17)") (class "Default")
      (node (ref "U2") (pin "17") (pinfunction "VBAT_17") (pintype "passive"))
    )
    (net (code "119") (name "unconnected-(U3-Pad1)") (class "Default")
      (node (ref "U3") (pin "1") (pinfunction "1_1") (pintype "bidirectional"))
    )
    (net (code "120") (name "unconnected-(U3-Pad2)") (class "Default")
      (node (ref "U3") (pin "2") (pinfunction "2_2") (pintype "bidirectional"))
    )
    (net (code "121") (name "unconnected-(U4-AREF{slash}A6-PadADC_VREF)") (class "Default")
      (node (ref "U4") (pin "ADC_VREF") (pinfunction "AREF/A6_ADC_VREF") (pintype "bidirectional"))
    )
    (net (code "122") (name "unconnected-(U4-D5{slash}CC-PadD5)") (class "Default")
      (node (ref "U4") (pin "D5") (pinfunction "D5/CC_D5") (pintype "bidirectional"))
    )
    (net (code "123") (name "unconnected-(U4-D13{slash}LED-PadD13)") (class "Default")
      (node (ref "U4") (pin "D13") (pinfunction "D13/LED_D13") (pintype "bidirectional"))
    )
    (net (code "124") (name "unconnected-(U4-D14{slash}A0-PadD14)") (class "Default")
      (node (ref "U4") (pin "D14") (pinfunction "D14/A0_D14") (pintype "bidirectional"))
    )
    (net (code "125") (name "unconnected-(U4-D15{slash}A1-PadD15)") (class "Default")
      (node (ref "U4") (pin "D15") (pinfunction "D15/A1_D15") (pintype "bidirectional"))
    )
    (net (code "126") (name "unconnected-(U4-D16{slash}A2-PadD16)") (class "Default")
      (node (ref "U4") (pin "D16") (pinfunction "D16/A2_D16") (pintype "bidirectional"))
    )
    (net (code "127") (name "unconnected-(U4-D17{slash}A3-PadD17)") (class "Default")
      (node (ref "U4") (pin "D17") (pinfunction "D17/A3_D17") (pintype "bidirectional"))
    )
    (net (code "128") (name "unconnected-(U4-D18{slash}A4-PadD18)") (class "Default")
      (node (ref "U4") (pin "D18") (pinfunction "D18/A4_D18") (pintype "bidirectional"))
    )
    (net (code "129") (name "unconnected-(U4-D19{slash}A5-PadD19)") (class "Default")
      (node (ref "U4") (pin "D19") (pinfunction "D19/A5_D19") (pintype "bidirectional"))
    )
    (net (code "130") (name "unconnected-(U4-D22{slash}SDA-PadD22)") (class "Default")
      (node (ref "U4") (pin "D22") (pinfunction "D22/SDA_D22") (pintype "bidirectional"))
    )
    (net (code "131") (name "unconnected-(U4-D23{slash}SCL-PadD23)") (class "Default")
      (node (ref "U4") (pin "D23") (pinfunction "D23/SCL_D23") (pintype "bidirectional"))
    )
    (net (code "132") (name "unconnected-(U4-D24{slash}MISO-PadD24)") (class "Default")
      (node (ref "U4") (pin "D24") (pinfunction "D24/MISO_D24") (pintype "bidirectional"))
    )
    (net (code "133") (name "unconnected-(U4-D25{slash}MOSI-PadD25)") (class "Default")
      (node (ref "U4") (pin "D25") (pinfunction "D25/MOSI_D25") (pintype "bidirectional"))
    )
    (net (code "134") (name "unconnected-(U4-D26{slash}SCK-PadD26)") (class "Default")
      (node (ref "U4") (pin "D26") (pinfunction "D26/SCK_D26") (pintype "bidirectional"))
    )
    (net (code "135") (name "unconnected-(U4-GND-PadGND@1)") (class "Default")
      (node (ref "U4") (pin "GND@1") (pinfunction "GND_GND@1") (pintype "bidirectional"))
    )
    (net (code "136") (name "unconnected-(U4-GND-PadGND@2)") (class "Default")
      (node (ref "U4") (pin "GND@2") (pinfunction "GND_GND@2") (pintype "bidirectional"))
    )
    (net (code "137") (name "unconnected-(U4-Pad3V3)") (class "Default")
      (node (ref "U4") (pin "3V3") (pinfunction "3V3_3V3") (pintype "bidirectional"))
    )
    (net (code "138") (name "unconnected-(U4-PadD+)") (class "Default")
      (node (ref "U4") (pin "D+") (pinfunction "D+_D+") (pintype "bidirectional"))
    )
    (net (code "139") (name "unconnected-(U4-PadD-)") (class "Default")
      (node (ref "U4") (pin "D-") (pinfunction "D-_D-") (pintype "bidirectional"))
    )
    (net (code "140") (name "unconnected-(U4-PadD0)") (class "Default")
      (node (ref "U4") (pin "D0") (pinfunction "D0_D0") (pintype "bidirectional"))
    )
    (net (code "141") (name "unconnected-(U4-PadD1)") (class "Default")
      (node (ref "U4") (pin "D1") (pinfunction "D1_D1") (pintype "bidirectional"))
    )
    (net (code "142") (name "unconnected-(U4-PadD2)") (class "Default")
      (node (ref "U4") (pin "D2") (pinfunction "D2_D2") (pintype "bidirectional"))
    )
    (net (code "143") (name "unconnected-(U4-PadD6)") (class "Default")
      (node (ref "U4") (pin "D6") (pinfunction "D6_D6") (pintype "bidirectional"))
    )
    (net (code "144") (name "unconnected-(U4-PadD9)") (class "Default")
      (node (ref "U4") (pin "D9") (pinfunction "D9_D9") (pintype "bidirectional"))
    )
    (net (code "145") (name "unconnected-(U4-PadD10)") (class "Default")
      (node (ref "U4") (pin "D10") (pinfunction "D10_D10") (pintype "bidirectional"))
    )
    (net (code "146") (name "unconnected-(U4-PadD11)") (class "Default")
      (node (ref "U4") (pin "D11") (pinfunction "D11_D11") (pintype "bidirectional"))
    )
    (net (code "147") (name "unconnected-(U4-PadD12)") (class "Default")
      (node (ref "U4") (pin "D12") (pinfunction "D12_D12") (pintype "bidirectional"))
    )
    (net (code "148") (name "unconnected-(U4-PadRESET)") (class "Default")
      (node (ref "U4") (pin "RESET") (pinfunction "RESET_RESET") (pintype "bidirectional"))
    )
    (net (code "149") (name "unconnected-(U4-PadVBUS)") (class "Default")
      (node (ref "U4") (pin "VBUS") (pinfunction "VBUS_VBUS") (pintype "bidirectional"))
    )
    (net (code "150") (name "unconnected-(X1-GND-PadGND@1)") (class "Default")
      (node (ref "X1") (pin "GND@1") (pinfunction "GND_GND@1") (pintype "bidirectional"))
    )
    (net (code "151") (name "unconnected-(X1-GND-PadGND@2)") (class "Default")
      (node (ref "X1") (pin "GND@2") (pinfunction "GND_GND@2") (pintype "bidirectional"))
    )
    (net (code "152") (name "unconnected-(X1-GND-PadGND@3)") (class "Default")
      (node (ref "X1") (pin "GND@3") (pinfunction "GND_GND@3") (pintype "bidirectional"))
    )
    (net (code "153") (name "unconnected-(X1-GND-PadGND@4)") (class "Default")
      (node (ref "X1") (pin "GND@4") (pinfunction "GND_GND@4") (pintype "bidirectional"))
    )
    (net (code "154") (name "unconnected-(X1-GND-PadGND@6)") (class "Default")
      (node (ref "X1") (pin "GND@6") (pinfunction "GND_GND@6") (pintype "bidirectional"))
    )
    (net (code "155") (name "unconnected-(X1-GND-PadGND@7)") (class "Default")
      (node (ref "X1") (pin "GND@7") (pinfunction "GND_GND@7") (pintype "bidirectional"))
    )
    (net (code "156") (name "unconnected-(X1-Pad3V3_EN)") (class "Default")
      (node (ref "X1") (pin "3V3_EN") (pinfunction "3V3_EN_3V3_EN") (pintype "bidirectional"))
    )
    (net (code "157") (name "unconnected-(X1-PadAGND)") (class "Default")
      (node (ref "X1") (pin "AGND") (pinfunction "AGND_AGND") (pintype "bidirectional"))
    )
    (net (code "158") (name "unconnected-(X1-PadGP2)") (class "Default")
      (node (ref "X1") (pin "GP2") (pinfunction "GP2_GP2") (pintype "bidirectional"))
    )
    (net (code "159") (name "unconnected-(X1-PadGP3)") (class "Default")
      (node (ref "X1") (pin "GP3") (pinfunction "GP3_GP3") (pintype "bidirectional"))
    )
    (net (code "160") (name "unconnected-(X1-PadGP7)") (class "Default")
      (node (ref "X1") (pin "GP7") (pinfunction "GP7_GP7") (pintype "bidirectional"))
    )
    (net (code "161") (name "unconnected-(X1-PadGP8)") (class "Default")
      (node (ref "X1") (pin "GP8") (pinfunction "GP8_GP8") (pintype "bidirectional"))
    )
    (net (code "162") (name "unconnected-(X1-PadGP9)") (class "Default")
      (node (ref "X1") (pin "GP9") (pinfunction "GP9_GP9") (pintype "bidirectional"))
    )
    (net (code "163") (name "unconnected-(X1-PadGP10)") (class "Default")
      (node (ref "X1") (pin "GP10") (pinfunction "GP10_GP10") (pintype "bidirectional"))
    )
    (net (code "164") (name "unconnected-(X1-PadGP16)") (class "Default")
      (node (ref "X1") (pin "GP16") (pinfunction "GP16_GP16") (pintype "bidirectional"))
    )
    (net (code "165") (name "unconnected-(X1-PadGP17)") (class "Default")
      (node (ref "X1") (pin "GP17") (pinfunction "GP17_GP17") (pintype "bidirectional"))
    )
  )
)
